# USB_OUT_A.net
KiCad netlist of a schematic drawn in Altium Designer
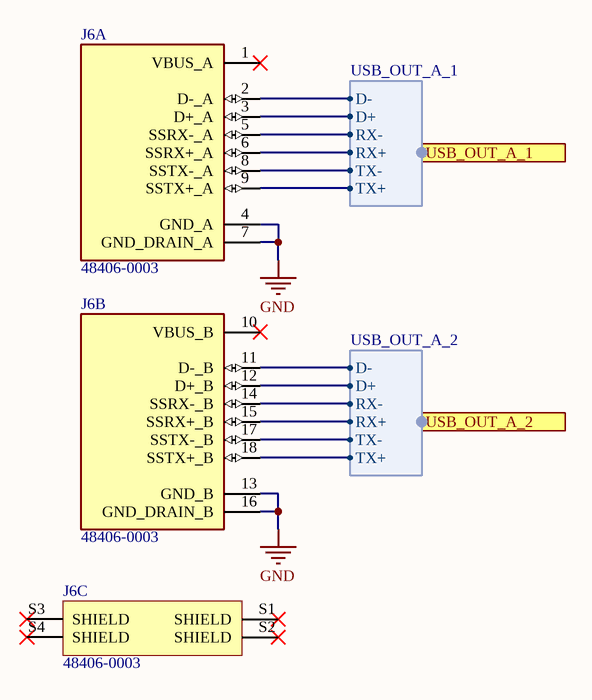
[diagram p0: USB_OUT_A.SchDoc]

(export (version "E")
  (design (tool "Eeschema 10.0.6"))
  (components
    (comp (ref "J6")
      (value "48406-0003")
      (footprint "MOLEX_48406")
      (fields (field (name "MF") "Molex"))
      (libsource (lib "KVM Library") (part "48406-0003"))
    )
  )
  (nets
    (net (code "5") (name "GND") (class "Default")
      (node (ref "J6") (pin "13") (pinfunction "GND_B_13") (pintype "power_in"))
      (node (ref "J6") (pin "16") (pinfunction "GND_DRAIN_B_16") (pintype "power_in"))
      (node (ref "J6") (pin "4") (pinfunction "GND_A_4") (pintype "power_in"))
      (node (ref "J6") (pin "7") (pinfunction "GND_DRAIN_A_7") (pintype "power_in"))
    )
    (net (code "6") (name "unconnected-(J6A-D+_A-Pad3)") (class "Default")
      (node (ref "J6") (pin "3") (pinfunction "D+_A_3") (pintype "bidirectional"))
    )
    (net (code "7") (name "unconnected-(J6A-D-_A-Pad2)") (class "Default")
      (node (ref "J6") (pin "2") (pinfunction "D-_A_2") (pintype "bidirectional"))
    )
    (net (code "8") (name "unconnected-(J6A-SSRX+_A-Pad6)") (class "Default")
      (node (ref "J6") (pin "6") (pinfunction "SSRX+_A_6") (pintype "bidirectional"))
    )
    (net (code "9") (name "unconnected-(J6A-SSRX-_A-Pad5)") (class "Default")
      (node (ref "J6") (pin "5") (pinfunction "SSRX-_A_5") (pintype "bidirectional"))
    )
    (net (code "10") (name "unconnected-(J6A-SSTX+_A-Pad9)") (class "Default")
      (node (ref "J6") (pin "9") (pinfunction "SSTX+_A_9") (pintype "bidirectional"))
    )
    (net (code "11") (name "unconnected-(J6A-SSTX-_A-Pad8)") (class "Default")
      (node (ref "J6") (pin "8") (pinfunction "SSTX-_A_8") (pintype "bidirectional"))
    )
    (net (code "12") (name "unconnected-(J6A-VBUS_A-Pad1)") (class "Default")
      (node (ref "J6") (pin "1") (pinfunction "VBUS_A_1") (pintype "power_in+no_connect"))
    )
    (net (code "13") (name "unconnected-(J6B-D+_B-Pad12)") (class "Default")
      (node (ref "J6") (pin "12") (pinfunction "D+_B_12") (pintype "bidirectional"))
    )
    (net (code "14") (name "unconnected-(J6B-D-_B-Pad11)") (class "Default")
      (node (ref "J6") (pin "11") (pinfunction "D-_B_11") (pintype "bidirectional"))
    )
    (net (code "15") (name "unconnected-(J6B-SSRX+_B-Pad15)") (class "Default")
      (node (ref "J6") (pin "15") (pinfunction "SSRX+_B_15") (pintype "bidirectional"))
    )
    (net (code "16") (name "unconnected-(J6B-SSRX-_B-Pad14)") (class "Default")
      (node (ref "J6") (pin "14") (pinfunction "SSRX-_B_14") (pintype "bidirectional"))
    )
    (net (code "17") (name "unconnected-(J6B-SSTX+_B-Pad18)") (class "Default")
      (node (ref "J6") (pin "18") (pinfunction "SSTX+_B_18") (pintype "bidirectional"))
    )
    (net (code "18") (name "unconnected-(J6B-SSTX-_B-Pad17)") (class "Default")
      (node (ref "J6") (pin "17") (pinfunction "SSTX-_B_17") (pintype "bidirectional"))
    )
    (net (code "19") (name "unconnected-(J6B-VBUS_B-Pad10)") (class "Default")
      (node (ref "J6") (pin "10") (pinfunction "VBUS_B_10") (pintype "power_in+no_connect"))
    )
    (net (code "20") (name "unconnected-(J6C-SHIELD-PadS1)") (class "Default")
      (node (ref "J6") (pin "S1") (pinfunction "SHIELD_S1") (pintype "passive+no_connect"))
    )
    (net (code "21") (name "unconnected-(J6C-SHIELD-PadS2)") (class "Default")
      (node (ref "J6") (pin "S2") (pinfunction "SHIELD_S2") (pintype "passive+no_connect"))
    )
    (net (code "22") (name "unconnected-(J6C-SHIELD-PadS3)") (class "Default")
      (node (ref "J6") (pin "S3") (pinfunction "SHIELD_S3") (pintype "passive+no_connect"))
    )
    (net (code "23") (name "unconnected-(J6C-SHIELD-PadS4)") (class "Default")
      (node (ref "J6") (pin "S4") (pinfunction "SHIELD_S4") (pintype "passive+no_connect"))
    )
  )
)
